# Modular_BO.net
KiCad netlist of a schematic drawn in Altium Designer
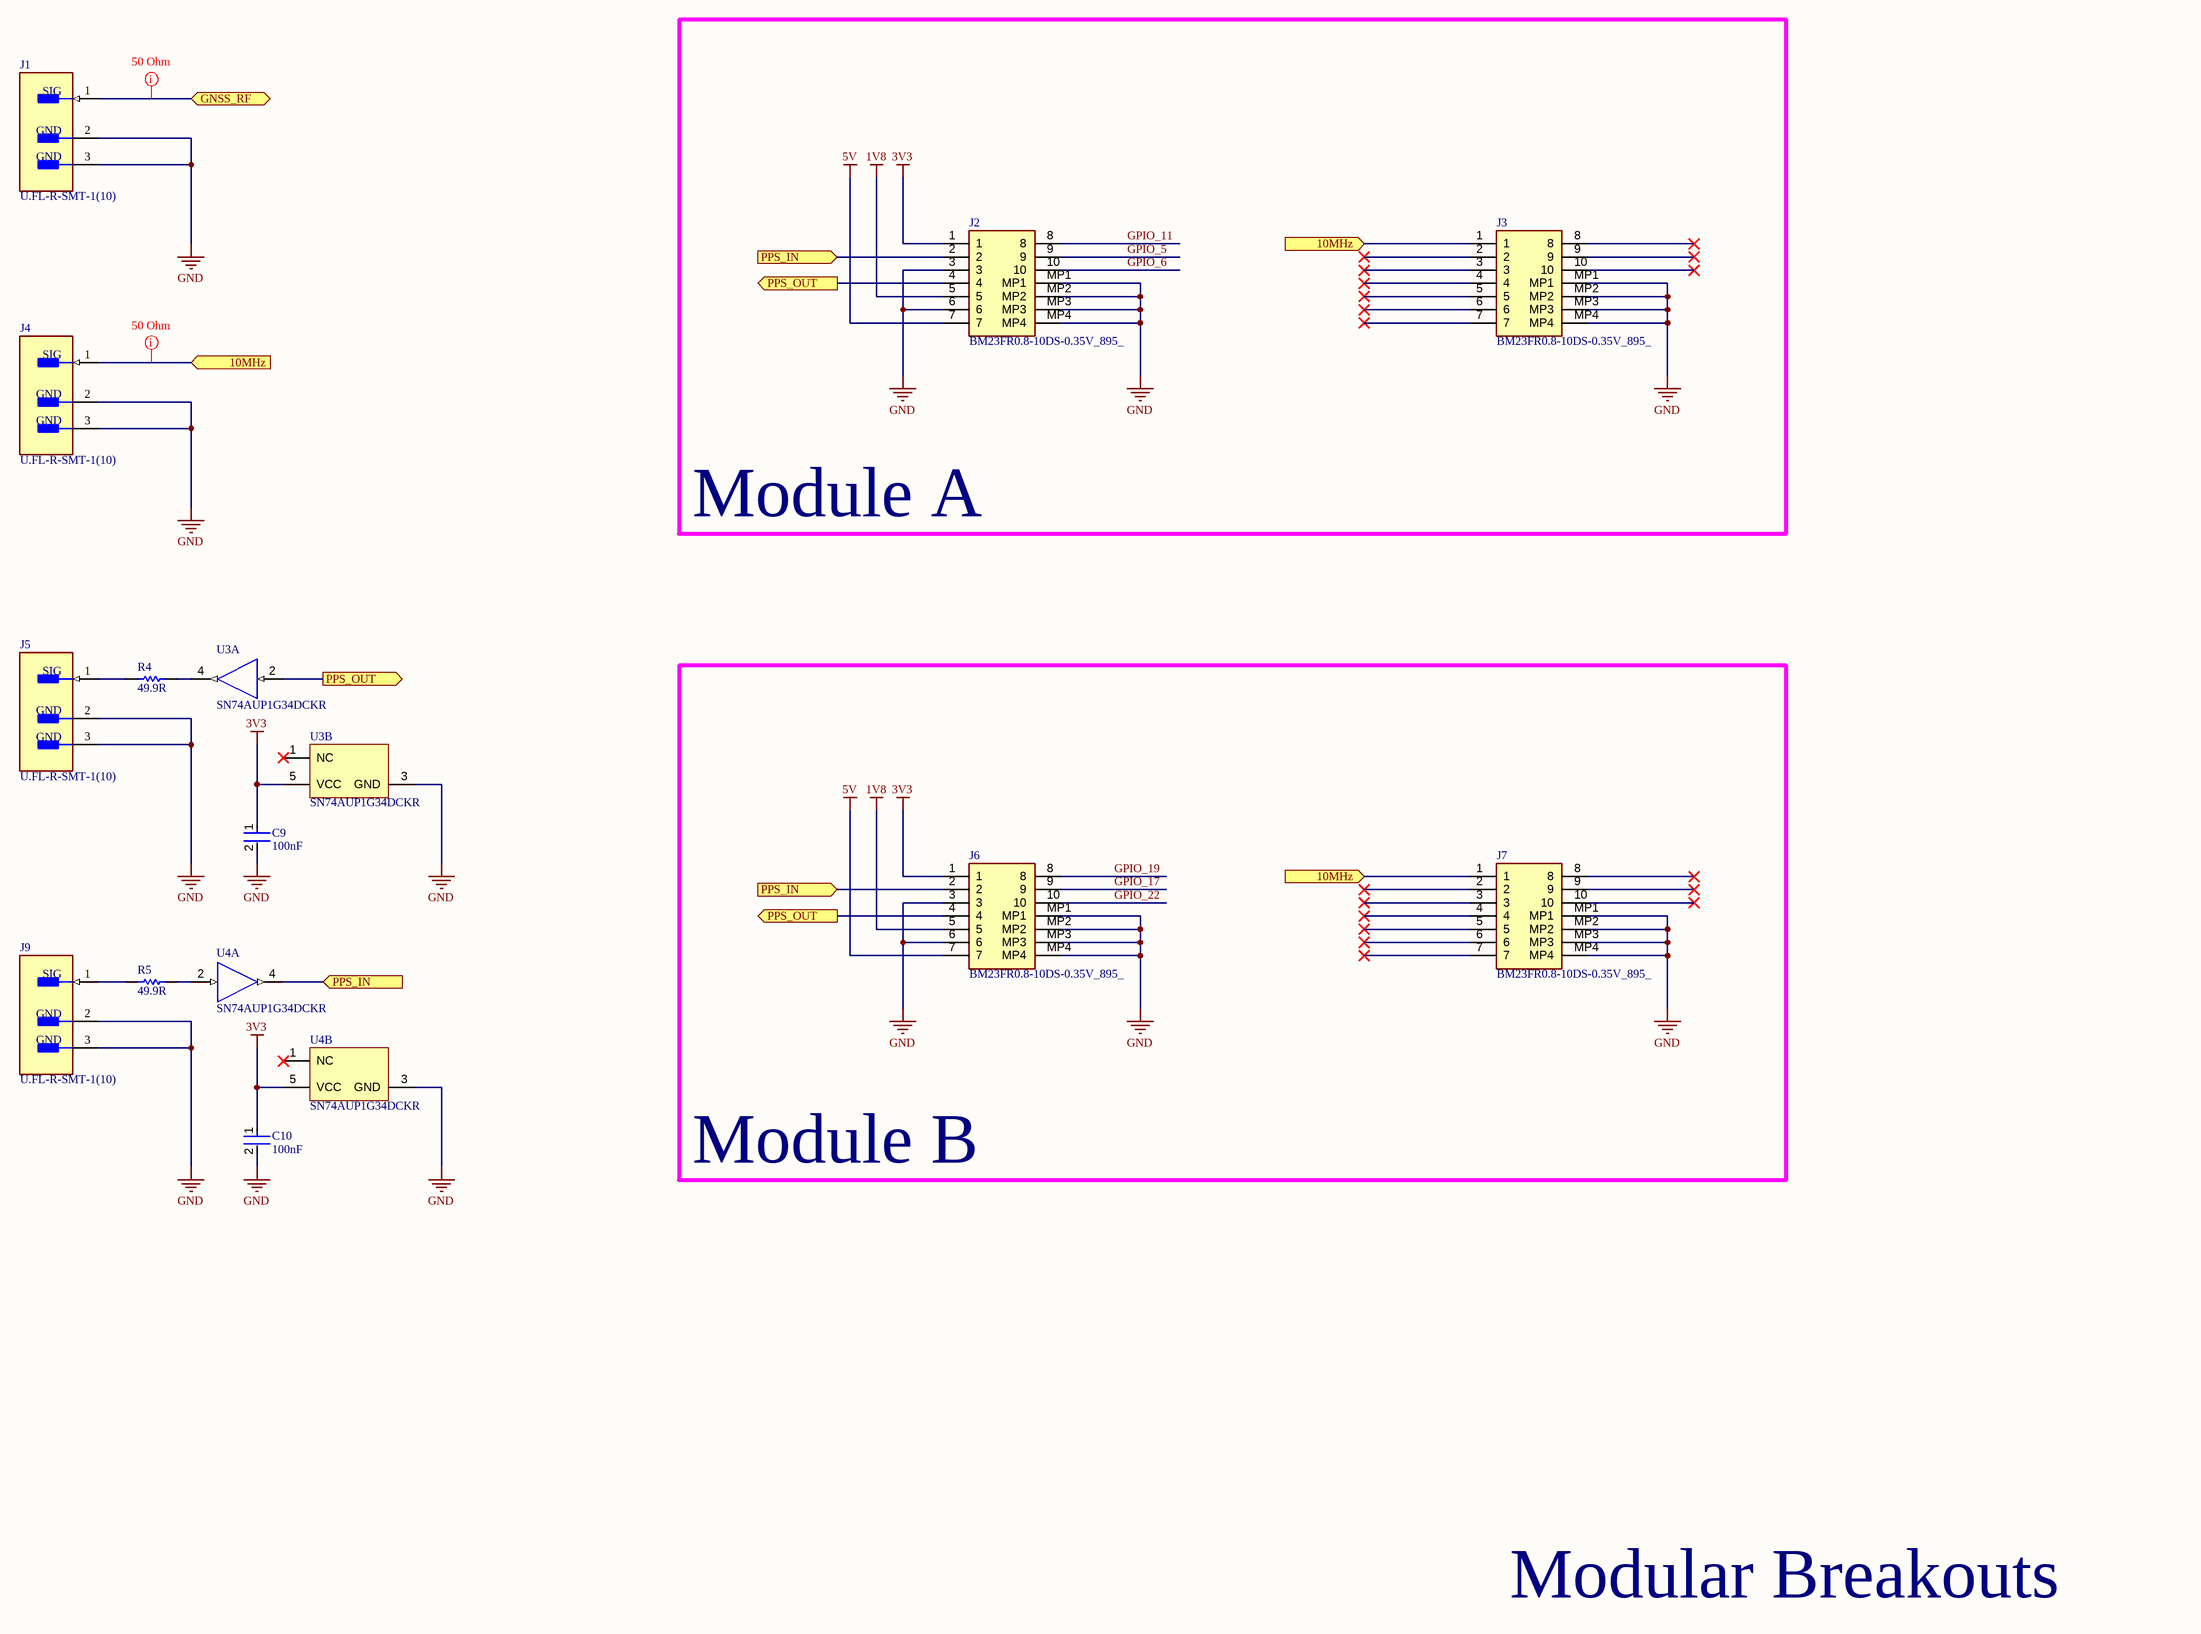
[diagram p0: Modular_BO.SchDoc]

(export (version "E")
  (design (tool "Eeschema 10.0.6"))
  (components
    (comp (ref "C9")
      (value "100nF")
      (footprint "FP-C0603C-CF-MFG")
      (description "CAP CER 0.1UF 50V 20% X7R 0603")
      (fields
        (field (name "MANUFACTURER PART NUMBER") "C0603C104M5RACTU")
        (field (name "MANUFACTURER") "KEMET")
      )
      (libsource (lib "Altium Content Vault") (part "b4654b650e69147ec39a6b967a45e02"))
    )
    (comp (ref "C10")
      (value "100nF")
      (footprint "FP-C0603C-CF-MFG")
      (description "CAP CER 0.1UF 50V 20% X7R 0603")
      (fields
        (field (name "MANUFACTURER PART NUMBER") "C0603C104M5RACTU")
        (field (name "MANUFACTURER") "KEMET")
      )
      (libsource (lib "Altium Content Vault") (part "b4654b650e69147ec39a6b967a45e02"))
    )
    (comp (ref "J1")
      (value "U.FL-R-SMT-1(10)")
      (footprint "FP-U_FL-R-SMT-1_10-MFG")
      (description "CONN U.FL RCPT STR 50 OHM SMD")
      (libsource (lib "Altium Content Vault") (part "7158abf7d987fa84906f6fb0d115710"))
    )
    (comp (ref "J2")
      (value "BM23FR0.8-10DS-0.35V_895_")
      (footprint "SamacSys:BM23FR0810DS035V895")
      (description "Connector")
      (fields
        (field (name "MANUFACTURER_PART_NUMBER") "BM23FR0.8-10DS-0.35V(895)")
        (field (name "MOUSER PART NUMBER") "798-3FR0810DS035V895")
      )
      (libsource (lib "*") (part "BM23FR0.8-10DS-0.35V_895_"))
    )
    (comp (ref "J3")
      (value "BM23FR0.8-10DS-0.35V_895_")
      (footprint "SamacSys:BM23FR0810DS035V895")
      (description "Connector")
      (fields
        (field (name "MANUFACTURER_PART_NUMBER") "BM23FR0.8-10DS-0.35V(895)")
        (field (name "MOUSER PART NUMBER") "798-3FR0810DS035V895")
      )
      (libsource (lib "*") (part "BM23FR0.8-10DS-0.35V_895_"))
    )
    (comp (ref "J4")
      (value "U.FL-R-SMT-1(10)")
      (footprint "FP-U_FL-R-SMT-1_10-MFG")
      (description "CONN U.FL RCPT STR 50 OHM SMD")
      (libsource (lib "Altium Content Vault") (part "7158abf7d987fa84906f6fb0d115710"))
    )
    (comp (ref "J5")
      (value "U.FL-R-SMT-1(10)")
      (footprint "FP-U_FL-R-SMT-1_10-MFG")
      (description "CONN U.FL RCPT STR 50 OHM SMD")
      (libsource (lib "Altium Content Vault") (part "7158abf7d987fa84906f6fb0d115710"))
    )
    (comp (ref "J6")
      (value "BM23FR0.8-10DS-0.35V_895_")
      (footprint "SamacSys:BM23FR0810DS035V895")
      (description "Connector")
      (fields
        (field (name "MANUFACTURER_PART_NUMBER") "BM23FR0.8-10DS-0.35V(895)")
        (field (name "MOUSER PART NUMBER") "798-3FR0810DS035V895")
      )
      (libsource (lib "*") (part "BM23FR0.8-10DS-0.35V_895_"))
    )
    (comp (ref "J7")
      (value "BM23FR0.8-10DS-0.35V_895_")
      (footprint "SamacSys:BM23FR0810DS035V895")
      (description "Connector")
      (fields
        (field (name "MANUFACTURER_PART_NUMBER") "BM23FR0.8-10DS-0.35V(895)")
        (field (name "MOUSER PART NUMBER") "798-3FR0810DS035V895")
      )
      (libsource (lib "*") (part "BM23FR0.8-10DS-0.35V_895_"))
    )
    (comp (ref "J9")
      (value "U.FL-R-SMT-1(10)")
      (footprint "FP-U_FL-R-SMT-1_10-MFG")
      (description "CONN U.FL RCPT STR 50 OHM SMD")
      (libsource (lib "Altium Content Vault") (part "7158abf7d987fa84906f6fb0d115710"))
    )
    (comp (ref "R4")
      (value "49.9R")
      (footprint "RESC1608X55X25NL10T15")
      (libsource (lib "Altium Content Vault") (part "RES-2"))
    )
    (comp (ref "R5")
      (value "49.9R")
      (footprint "RESC1608X55X25NL10T15")
      (libsource (lib "Altium Content Vault") (part "RES-2"))
    )
    (comp (ref "U3")
      (value "SN74AUP1G34DCKR")
      (footprint "DCK0005A_M")
      (description "Low-Power Single Buffer Gate, DCK0005A, LARGE T&R")
      (fields
        (field (name "GENERIC PART NUMBER") "SN74AUP1G34")
        (field (name "MANUFACTURER") "Texas Instruments")
      )
      (libsource (lib "") (part "TI-SN74XXX1XXX-XX-5_1"))
    )
    (comp (ref "U4")
      (value "SN74AUP1G34DCKR")
      (footprint "DCK0005A_M")
      (description "Low-Power Single Buffer Gate, DCK0005A, LARGE T&R")
      (fields
        (field (name "GENERIC PART NUMBER") "SN74AUP1G34")
        (field (name "MANUFACTURER") "Texas Instruments")
      )
      (libsource (lib "") (part "TI-SN74XXX1XXX-XX-5_1"))
    )
  )
  (nets
    (net (code "1") (name "/10MHz") (class "Default")
      (node (ref "J3") (pin "1") (pinfunction "1_1") (pintype "passive"))
      (node (ref "J4") (pin "1") (pinfunction "SIG_1") (pintype "input"))
      (node (ref "J7") (pin "1") (pinfunction "1_1") (pintype "passive"))
    )
    (net (code "2") (name "/GNSS_RF") (class "Default")
      (node (ref "J1") (pin "1") (pinfunction "SIG_1") (pintype "input"))
    )
    (net (code "3") (name "/GPIO_5") (class "Default")
      (node (ref "J2") (pin "9") (pinfunction "9_9") (pintype "passive"))
    )
    (net (code "4") (name "/GPIO_6") (class "Default")
      (node (ref "J2") (pin "10") (pinfunction "10_10") (pintype "passive"))
    )
    (net (code "5") (name "/GPIO_11") (class "Default")
      (node (ref "J2") (pin "8") (pinfunction "8_8") (pintype "passive"))
    )
    (net (code "6") (name "/GPIO_17") (class "Default")
      (node (ref "J6") (pin "9") (pinfunction "9_9") (pintype "passive"))
    )
    (net (code "7") (name "/GPIO_19") (class "Default")
      (node (ref "J6") (pin "8") (pinfunction "8_8") (pintype "passive"))
    )
    (net (code "8") (name "/GPIO_22") (class "Default")
      (node (ref "J6") (pin "10") (pinfunction "10_10") (pintype "passive"))
    )
    (net (code "9") (name "/PPS_IN") (class "Default")
      (node (ref "J2") (pin "2") (pinfunction "2_2") (pintype "passive"))
      (node (ref "J6") (pin "2") (pinfunction "2_2") (pintype "passive"))
      (node (ref "U4") (pin "4") (pinfunction "Y_4") (pintype "output"))
    )
    (net (code "10") (name "/PPS_OUT") (class "Default")
      (node (ref "J2") (pin "4") (pinfunction "4_4") (pintype "passive"))
      (node (ref "J6") (pin "4") (pinfunction "4_4") (pintype "passive"))
      (node (ref "U3") (pin "2") (pinfunction "A_2") (pintype "input"))
    )
    (net (code "11") (name "1V8") (class "Default")
      (node (ref "J2") (pin "5") (pinfunction "5_5") (pintype "passive"))
      (node (ref "J6") (pin "5") (pinfunction "5_5") (pintype "passive"))
    )
    (net (code "12") (name "3V3") (class "Default")
      (node (ref "C10") (pin "1") (pinfunction "1_1") (pintype "passive"))
      (node (ref "C9") (pin "1") (pinfunction "1_1") (pintype "passive"))
      (node (ref "J2") (pin "1") (pinfunction "1_1") (pintype "passive"))
      (node (ref "J6") (pin "1") (pinfunction "1_1") (pintype "passive"))
      (node (ref "U3") (pin "5") (pinfunction "VCC_5") (pintype "power_in"))
      (node (ref "U4") (pin "5") (pinfunction "VCC_5") (pintype "power_in"))
    )
    (net (code "13") (name "5V") (class "Default")
      (node (ref "J2") (pin "7") (pinfunction "7_7") (pintype "passive"))
      (node (ref "J6") (pin "7") (pinfunction "7_7") (pintype "passive"))
    )
    (net (code "14") (name "GND") (class "Default")
      (node (ref "C10") (pin "2") (pinfunction "2_2") (pintype "passive"))
      (node (ref "C9") (pin "2") (pinfunction "2_2") (pintype "passive"))
      (node (ref "J1") (pin "2") (pinfunction "GND_2") (pintype "power_in"))
      (node (ref "J1") (pin "3") (pinfunction "GND_3") (pintype "power_in"))
      (node (ref "J2") (pin "3") (pinfunction "3_3") (pintype "passive"))
      (node (ref "J2") (pin "6") (pinfunction "6_6") (pintype "passive"))
      (node (ref "J2") (pin "MP1") (pinfunction "MP1_MP1") (pintype "passive"))
      (node (ref "J2") (pin "MP2") (pinfunction "MP2_MP2") (pintype "passive"))
      (node (ref "J2") (pin "MP3") (pinfunction "MP3_MP3") (pintype "passive"))
      (node (ref "J2") (pin "MP4") (pinfunction "MP4_MP4") (pintype "passive"))
      (node (ref "J3") (pin "MP1") (pinfunction "MP1_MP1") (pintype "passive"))
      (node (ref "J3") (pin "MP2") (pinfunction "MP2_MP2") (pintype "passive"))
      (node (ref "J3") (pin "MP3") (pinfunction "MP3_MP3") (pintype "passive"))
      (node (ref "J3") (pin "MP4") (pinfunction "MP4_MP4") (pintype "passive"))
      (node (ref "J4") (pin "2") (pinfunction "GND_2") (pintype "power_in"))
      (node (ref "J4") (pin "3") (pinfunction "GND_3") (pintype "power_in"))
      (node (ref "J5") (pin "2") (pinfunction "GND_2") (pintype "power_in"))
      (node (ref "J5") (pin "3") (pinfunction "GND_3") (pintype "power_in"))
      (node (ref "J6") (pin "3") (pinfunction "3_3") (pintype "passive"))
      (node (ref "J6") (pin "6") (pinfunction "6_6") (pintype "passive"))
      (node (ref "J6") (pin "MP1") (pinfunction "MP1_MP1") (pintype "passive"))
      (node (ref "J6") (pin "MP2") (pinfunction "MP2_MP2") (pintype "passive"))
      (node (ref "J6") (pin "MP3") (pinfunction "MP3_MP3") (pintype "passive"))
      (node (ref "J6") (pin "MP4") (pinfunction "MP4_MP4") (pintype "passive"))
      (node (ref "J7") (pin "MP1") (pinfunction "MP1_MP1") (pintype "passive"))
      (node (ref "J7") (pin "MP2") (pinfunction "MP2_MP2") (pintype "passive"))
      (node (ref "J7") (pin "MP3") (pinfunction "MP3_MP3") (pintype "passive"))
      (node (ref "J7") (pin "MP4") (pinfunction "MP4_MP4") (pintype "passive"))
      (node (ref "J9") (pin "2") (pinfunction "GND_2") (pintype "power_in"))
      (node (ref "J9") (pin "3") (pinfunction "GND_3") (pintype "power_in"))
      (node (ref "U3") (pin "3") (pinfunction "GND_3") (pintype "power_in"))
      (node (ref "U4") (pin "3") (pinfunction "GND_3") (pintype "power_in"))
    )
    (net (code "15") (name "Net-(J5-SIG)") (class "Default")
      (node (ref "J5") (pin "1") (pinfunction "SIG_1") (pintype "input"))
      (node (ref "R4") (pin "1") (pinfunction "1_1") (pintype "passive"))
    )
    (net (code "16") (name "Net-(J9-SIG)") (class "Default")
      (node (ref "J9") (pin "1") (pinfunction "SIG_1") (pintype "input"))
      (node (ref "R5") (pin "1") (pinfunction "1_1") (pintype "passive"))
    )
    (net (code "17") (name "Net-(U3A-Y)") (class "Default")
      (node (ref "R4") (pin "2") (pinfunction "2_2") (pintype "passive"))
      (node (ref "U3") (pin "4") (pinfunction "Y_4") (pintype "output"))
    )
    (net (code "18") (name "Net-(U4A-A)") (class "Default")
      (node (ref "R5") (pin "2") (pinfunction "2_2") (pintype "passive"))
      (node (ref "U4") (pin "2") (pinfunction "A_2") (pintype "input"))
    )
    (net (code "19") (name "unconnected-(J3-Pad2)") (class "Default")
      (node (ref "J3") (pin "2") (pinfunction "2_2") (pintype "passive+no_connect"))
    )
    (net (code "20") (name "unconnected-(J3-Pad3)") (class "Default")
      (node (ref "J3") (pin "3") (pinfunction "3_3") (pintype "passive+no_connect"))
    )
    (net (code "21") (name "unconnected-(J3-Pad4)") (class "Default")
      (node (ref "J3") (pin "4") (pinfunction "4_4") (pintype "passive+no_connect"))
    )
    (net (code "22") (name "unconnected-(J3-Pad5)") (class "Default")
      (node (ref "J3") (pin "5") (pinfunction "5_5") (pintype "passive+no_connect"))
    )
    (net (code "23") (name "unconnected-(J3-Pad6)") (class "Default")
      (node (ref "J3") (pin "6") (pinfunction "6_6") (pintype "passive+no_connect"))
    )
    (net (code "24") (name "unconnected-(J3-Pad7)") (class "Default")
      (node (ref "J3") (pin "7") (pinfunction "7_7") (pintype "passive+no_connect"))
    )
    (net (code "25") (name "unconnected-(J3-Pad8)") (class "Default")
      (node (ref "J3") (pin "8") (pinfunction "8_8") (pintype "passive+no_connect"))
    )
    (net (code "26") (name "unconnected-(J3-Pad9)") (class "Default")
      (node (ref "J3") (pin "9") (pinfunction "9_9") (pintype "passive+no_connect"))
    )
    (net (code "27") (name "unconnected-(J3-Pad10)") (class "Default")
      (node (ref "J3") (pin "10") (pinfunction "10_10") (pintype "passive+no_connect"))
    )
    (net (code "28") (name "unconnected-(J7-Pad2)") (class "Default")
      (node (ref "J7") (pin "2") (pinfunction "2_2") (pintype "passive+no_connect"))
    )
    (net (code "29") (name "unconnected-(J7-Pad3)") (class "Default")
      (node (ref "J7") (pin "3") (pinfunction "3_3") (pintype "passive+no_connect"))
    )
    (net (code "30") (name "unconnected-(J7-Pad4)") (class "Default")
      (node (ref "J7") (pin "4") (pinfunction "4_4") (pintype "passive+no_connect"))
    )
    (net (code "31") (name "unconnected-(J7-Pad5)") (class "Default")
      (node (ref "J7") (pin "5") (pinfunction "5_5") (pintype "passive+no_connect"))
    )
    (net (code "32") (name "unconnected-(J7-Pad6)") (class "Default")
      (node (ref "J7") (pin "6") (pinfunction "6_6") (pintype "passive+no_connect"))
    )
    (net (code "33") (name "unconnected-(J7-Pad7)") (class "Default")
      (node (ref "J7") (pin "7") (pinfunction "7_7") (pintype "passive+no_connect"))
    )
    (net (code "34") (name "unconnected-(J7-Pad8)") (class "Default")
      (node (ref "J7") (pin "8") (pinfunction "8_8") (pintype "passive+no_connect"))
    )
    (net (code "35") (name "unconnected-(J7-Pad9)") (class "Default")
      (node (ref "J7") (pin "9") (pinfunction "9_9") (pintype "passive+no_connect"))
    )
    (net (code "36") (name "unconnected-(J7-Pad10)") (class "Default")
      (node (ref "J7") (pin "10") (pinfunction "10_10") (pintype "passive+no_connect"))
    )
    (net (code "37") (name "unconnected-(U3B-NC-Pad1)") (class "Default")
      (node (ref "U3") (pin "1") (pinfunction "NC_1") (pintype "passive+no_connect"))
    )
    (net (code "38") (name "unconnected-(U4B-NC-Pad1)") (class "Default")
      (node (ref "U4") (pin "1") (pinfunction "NC_1") (pintype "passive+no_connect"))
    )
  )
)
